# CAN_CTRL.net
KiCad netlist of a schematic drawn in Altium Designer
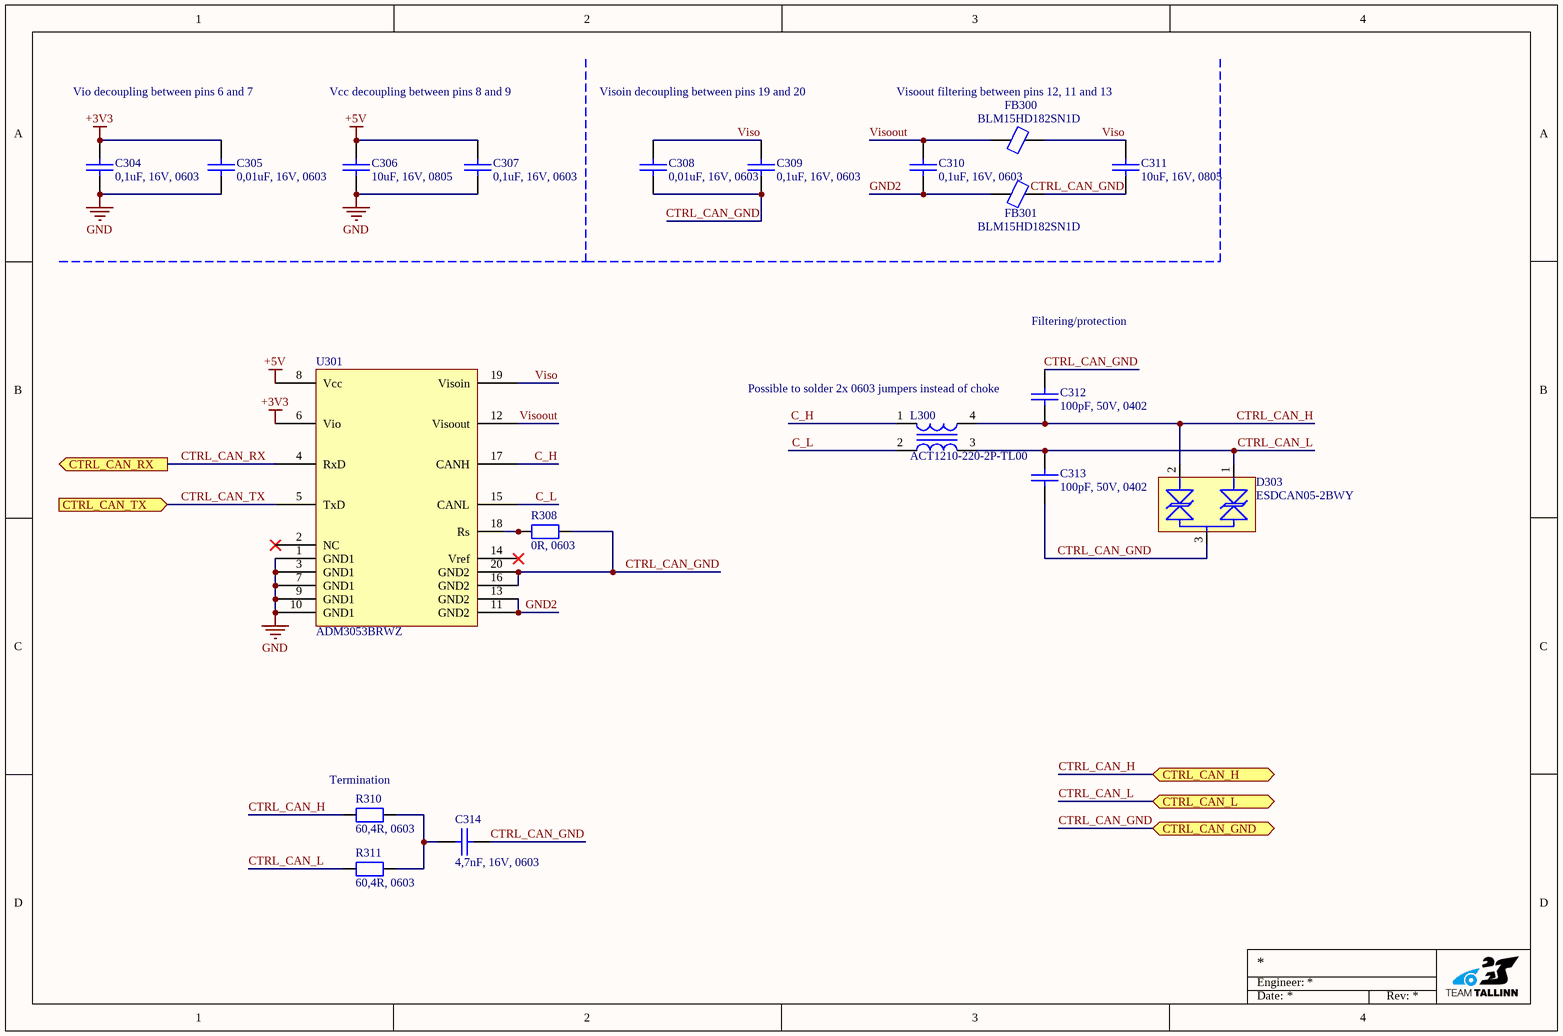
[diagram p0: CAN_CTRL.SchDoc]

(export (version "E")
  (design (tool "Eeschema 10.0.6"))
  (components
    (comp (ref "C304")
      (value "0,1uF, 16V, 0603")
      (footprint "CAP [0603] 1608")
      (description "Default capacitor part")
      (libsource (lib "Formula Student Team Tallinn (Estonia)") (part "Capacitor"))
    )
    (comp (ref "C305")
      (value "0,01uF, 16V, 0603")
      (footprint "CAP [0603] 1608")
      (description "Default capacitor part")
      (libsource (lib "Formula Student Team Tallinn (Estonia)") (part "Capacitor"))
    )
    (comp (ref "C306")
      (value "10uF, 16V, 0805")
      (footprint "CAP [0805] 2012")
      (description "Default capacitor part")
      (libsource (lib "Formula Student Team Tallinn (Estonia)") (part "Capacitor"))
    )
    (comp (ref "C307")
      (value "0,1uF, 16V, 0603")
      (footprint "CAP [0603] 1608")
      (description "Default capacitor part")
      (libsource (lib "Formula Student Team Tallinn (Estonia)") (part "Capacitor"))
    )
    (comp (ref "C308")
      (value "0,01uF, 16V, 0603")
      (footprint "CAP [0603] 1608")
      (description "Default capacitor part")
      (libsource (lib "Formula Student Team Tallinn (Estonia)") (part "Capacitor"))
    )
    (comp (ref "C309")
      (value "0,1uF, 16V, 0603")
      (footprint "CAP [0603] 1608")
      (description "Default capacitor part")
      (libsource (lib "Formula Student Team Tallinn (Estonia)") (part "Capacitor"))
    )
    (comp (ref "C310")
      (value "0,1uF, 16V, 0603")
      (footprint "CAP [0603] 1608")
      (description "Default capacitor part")
      (libsource (lib "Formula Student Team Tallinn (Estonia)") (part "Capacitor"))
    )
    (comp (ref "C311")
      (value "10uF, 16V, 0805")
      (footprint "CAP [0805] 2012")
      (description "Default capacitor part")
      (libsource (lib "Formula Student Team Tallinn (Estonia)") (part "Capacitor"))
    )
    (comp (ref "C312")
      (value "100pF, 50V, 0402")
      (footprint "CAP [0402] 1005")
      (description "Default capacitor part")
      (libsource (lib "Formula Student Team Tallinn (Estonia)") (part "Capacitor"))
    )
    (comp (ref "C313")
      (value "100pF, 50V, 0402")
      (footprint "CAP [0402] 1005")
      (description "Default capacitor part")
      (libsource (lib "Formula Student Team Tallinn (Estonia)") (part "Capacitor"))
    )
    (comp (ref "C314")
      (value "4,7nF, 16V, 0603")
      (footprint "CAP [0603] 1608")
      (description "Default capacitor part")
      (libsource (lib "Formula Student Team Tallinn (Estonia)") (part "Capacitor"))
    )
    (comp (ref "D303")
      (value "ESDCAN05-2BWY")
      (footprint "SOT323/SC70-3")
      (description "Trans Voltage Suppressor Diode, 170W, 36V V(RWM), Bidirectional, 2 Element, Silicon")
      (fields (field (name "MANUFACTURER") "STMicroelectronics"))
      (libsource (lib "Formula Student Team Tallinn (Estonia)") (part "Diode TVS Bidirectional dual"))
    )
    (comp (ref "FB300")
      (value "BLM15HD182SN1D")
      (footprint "IND [0402] 1005")
      (description "Ferrite Chip, 1 Function(s), 0.2A, 2 Pin(s)")
      (fields (field (name "MANUFACTURER") "Murata"))
      (libsource (lib "Formula Student Team Tallinn (Estonia)") (part "Ferrite Bead"))
    )
    (comp (ref "FB301")
      (value "BLM15HD182SN1D")
      (footprint "IND [0402] 1005")
      (description "Ferrite Chip, 1 Function(s), 0.2A, 2 Pin(s)")
      (fields (field (name "MANUFACTURER") "Murata"))
      (libsource (lib "Formula Student Team Tallinn (Estonia)") (part "Ferrite Bead"))
    )
    (comp (ref "L300")
      (value "ACT1210-220-2P-TL00")
      (footprint "1210 Choke/ 2x0603 RES")
      (description "Data Line Filter, 2 Function(s), 80V, 0.25A, 4 Pin(s)")
      (fields (field (name "MANUFACTURER") "TDK"))
      (libsource (lib "Formula Student Team Tallinn (Estonia)") (part "Common mode choke"))
    )
    (comp (ref "R308")
      (value "0R, 0603")
      (footprint "RES [0603] 1608")
      (description "Standard resistor part")
      (libsource (lib "Formula Student Team Tallinn (Estonia)") (part "Resistor"))
    )
    (comp (ref "R310")
      (value "60,4R, 0603")
      (footprint "RES [0603] 1608")
      (description "Standard resistor part")
      (libsource (lib "Formula Student Team Tallinn (Estonia)") (part "Resistor"))
    )
    (comp (ref "R311")
      (value "60,4R, 0603")
      (footprint "RES [0603] 1608")
      (description "Standard resistor part")
      (libsource (lib "Formula Student Team Tallinn (Estonia)") (part "Resistor"))
    )
    (comp (ref "U301")
      (value "ADM3053BRWZ")
      (footprint "SOIC-20")
      (description "Interface Circuit, 1-Trnsvr, PDSO20")
      (fields (field (name "MANUFACTURER") "Analog Devices"))
      (libsource (lib "Formula Student Team Tallinn (Estonia)") (part "CAN Tranciever{colon} Isolated"))
    )
  )
  (nets
    (net (code "1") (name "+3V3") (class "Default")
      (node (ref "C304") (pin "1") (pinfunction "1_1") (pintype "passive"))
      (node (ref "C305") (pin "1") (pinfunction "1_1") (pintype "passive"))
      (node (ref "U301") (pin "6") (pinfunction "Vio_6") (pintype "passive"))
    )
    (net (code "2") (name "+5V") (class "Default")
      (node (ref "C306") (pin "1") (pinfunction "1_1") (pintype "passive"))
      (node (ref "C307") (pin "1") (pinfunction "1_1") (pintype "passive"))
      (node (ref "U301") (pin "8") (pinfunction "Vcc_8") (pintype "passive"))
    )
    (net (code "3") (name "/CTRL_CAN_GND") (class "Default")
      (node (ref "C308") (pin "2") (pinfunction "2_2") (pintype "passive"))
      (node (ref "C309") (pin "2") (pinfunction "2_2") (pintype "passive"))
      (node (ref "C311") (pin "2") (pinfunction "2_2") (pintype "passive"))
      (node (ref "C312") (pin "2") (pinfunction "2_2") (pintype "passive"))
      (node (ref "C313") (pin "1") (pinfunction "1_1") (pintype "passive"))
      (node (ref "C314") (pin "2") (pinfunction "2_2") (pintype "passive"))
      (node (ref "D303") (pin "3") (pinfunction "3_3") (pintype "passive"))
      (node (ref "FB301") (pin "2") (pinfunction "2_2") (pintype "passive"))
      (node (ref "R308") (pin "1") (pinfunction "1_1") (pintype "passive"))
      (node (ref "U301") (pin "16") (pinfunction "GND2_16") (pintype "passive"))
      (node (ref "U301") (pin "20") (pinfunction "GND2_20") (pintype "passive"))
    )
    (net (code "4") (name "/CTRL_CAN_H") (class "Default")
      (node (ref "C312") (pin "1") (pinfunction "1_1") (pintype "passive"))
      (node (ref "D303") (pin "2") (pinfunction "2_2") (pintype "passive"))
      (node (ref "L300") (pin "4") (pinfunction "4_4") (pintype "passive"))
      (node (ref "R310") (pin "2") (pinfunction "2_2") (pintype "passive"))
    )
    (net (code "5") (name "/CTRL_CAN_L") (class "Default")
      (node (ref "C313") (pin "2") (pinfunction "2_2") (pintype "passive"))
      (node (ref "D303") (pin "1") (pinfunction "1_1") (pintype "passive"))
      (node (ref "L300") (pin "3") (pinfunction "3_3") (pintype "passive"))
      (node (ref "R311") (pin "2") (pinfunction "2_2") (pintype "passive"))
    )
    (net (code "6") (name "/CTRL_CAN_RX") (class "Default")
      (node (ref "U301") (pin "4") (pinfunction "RxD_4") (pintype "passive"))
    )
    (net (code "7") (name "/CTRL_CAN_TX") (class "Default")
      (node (ref "U301") (pin "5") (pinfunction "TxD_5") (pintype "passive"))
    )
    (net (code "8") (name "/C_H") (class "Default")
      (node (ref "L300") (pin "1") (pinfunction "1_1") (pintype "passive"))
      (node (ref "U301") (pin "17") (pinfunction "CANH_17") (pintype "passive"))
    )
    (net (code "9") (name "/C_L") (class "Default")
      (node (ref "L300") (pin "2") (pinfunction "2_2") (pintype "passive"))
      (node (ref "U301") (pin "15") (pinfunction "CANL_15") (pintype "passive"))
    )
    (net (code "10") (name "/GND2") (class "Default")
      (node (ref "C310") (pin "2") (pinfunction "2_2") (pintype "passive"))
      (node (ref "FB301") (pin "1") (pinfunction "1_1") (pintype "passive"))
      (node (ref "U301") (pin "11") (pinfunction "GND2_11") (pintype "passive"))
      (node (ref "U301") (pin "13") (pinfunction "GND2_13") (pintype "passive"))
    )
    (net (code "11") (name "/Viso") (class "Default")
      (node (ref "C308") (pin "1") (pinfunction "1_1") (pintype "passive"))
      (node (ref "C309") (pin "1") (pinfunction "1_1") (pintype "passive"))
      (node (ref "C311") (pin "1") (pinfunction "1_1") (pintype "passive"))
      (node (ref "FB300") (pin "2") (pinfunction "2_2") (pintype "passive"))
      (node (ref "U301") (pin "19") (pinfunction "Visoin_19") (pintype "passive"))
    )
    (net (code "12") (name "/Visoout") (class "Default")
      (node (ref "C310") (pin "1") (pinfunction "1_1") (pintype "passive"))
      (node (ref "FB300") (pin "1") (pinfunction "1_1") (pintype "passive"))
      (node (ref "U301") (pin "12") (pinfunction "Visoout_12") (pintype "passive"))
    )
    (net (code "13") (name "GND") (class "Default")
      (node (ref "C304") (pin "2") (pinfunction "2_2") (pintype "passive"))
      (node (ref "C305") (pin "2") (pinfunction "2_2") (pintype "passive"))
      (node (ref "C306") (pin "2") (pinfunction "2_2") (pintype "passive"))
      (node (ref "C307") (pin "2") (pinfunction "2_2") (pintype "passive"))
      (node (ref "U301") (pin "1") (pinfunction "GND1_1") (pintype "passive"))
      (node (ref "U301") (pin "10") (pinfunction "GND1_10") (pintype "passive"))
      (node (ref "U301") (pin "3") (pinfunction "GND1_3") (pintype "passive"))
      (node (ref "U301") (pin "7") (pinfunction "GND1_7") (pintype "passive"))
      (node (ref "U301") (pin "9") (pinfunction "GND1_9") (pintype "passive"))
    )
    (net (code "14") (name "Net-(C314-Pad1)") (class "Default")
      (node (ref "C314") (pin "1") (pinfunction "1_1") (pintype "passive"))
      (node (ref "R310") (pin "1") (pinfunction "1_1") (pintype "passive"))
      (node (ref "R311") (pin "1") (pinfunction "1_1") (pintype "passive"))
    )
    (net (code "15") (name "Net-(U301-Rs)") (class "Default")
      (node (ref "R308") (pin "2") (pinfunction "2_2") (pintype "passive"))
      (node (ref "U301") (pin "18") (pinfunction "Rs_18") (pintype "passive"))
    )
    (net (code "16") (name "unconnected-(U301-NC-Pad2)") (class "Default")
      (node (ref "U301") (pin "2") (pinfunction "NC_2") (pintype "passive+no_connect"))
    )
    (net (code "17") (name "unconnected-(U301-Vref-Pad14)") (class "Default")
      (node (ref "U301") (pin "14") (pinfunction "Vref_14") (pintype "passive+no_connect"))
    )
  )
)
